# Buttons.net
KiCad netlist of a schematic drawn in Altium Designer
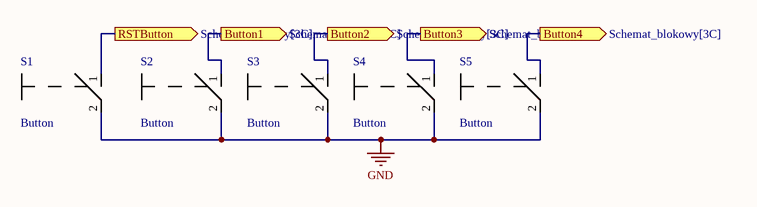
[diagram p0: Buttons.schdoc]

(export (version "E")
  (design (tool "Eeschema 10.0.6"))
  (components
    (comp (ref "S1")
      (value "Button")
      (footprint "SW_TL59NF160Q")
      (fields (field (name "PARTNUMBER") "TL59NF160Q"))
      (libsource (lib "Button") (part "Button"))
    )
    (comp (ref "S2")
      (value "Button")
      (footprint "SW_TL59NF160Q")
      (fields (field (name "PARTNUMBER") "TL59NF160Q"))
      (libsource (lib "Button") (part "Button"))
    )
    (comp (ref "S3")
      (value "Button")
      (footprint "SW_TL59NF160Q")
      (fields (field (name "PARTNUMBER") "TL59NF160Q"))
      (libsource (lib "Button") (part "Button"))
    )
    (comp (ref "S4")
      (value "Button")
      (footprint "SW_TL59NF160Q")
      (fields (field (name "PARTNUMBER") "TL59NF160Q"))
      (libsource (lib "Button") (part "Button"))
    )
    (comp (ref "S5")
      (value "Button")
      (footprint "SW_TL59NF160Q")
      (fields (field (name "PARTNUMBER") "TL59NF160Q"))
      (libsource (lib "Button") (part "Button"))
    )
  )
  (nets
    (net (code "1") (name "/Button1") (class "Default") (node (ref "S2") (pin "1") (pintype "passive")))
    (net (code "2") (name "/Button2") (class "Default") (node (ref "S3") (pin "1") (pintype "passive")))
    (net (code "3") (name "/Button3") (class "Default") (node (ref "S4") (pin "1") (pintype "passive")))
    (net (code "4") (name "/Button4") (class "Default") (node (ref "S5") (pin "1") (pintype "passive")))
    (net (code "5") (name "/RSTButton") (class "Default") (node (ref "S1") (pin "1") (pintype "passive")))
    (net (code "6") (name "GND") (class "Default")
      (node (ref "S1") (pin "2") (pintype "passive"))
      (node (ref "S2") (pin "2") (pintype "passive"))
      (node (ref "S3") (pin "2") (pintype "passive"))
      (node (ref "S4") (pin "2") (pintype "passive"))
      (node (ref "S5") (pin "2") (pintype "passive"))
    )
  )
)
